# camera_module_dev.net
KiCad netlist of a schematic drawn in EAGLE
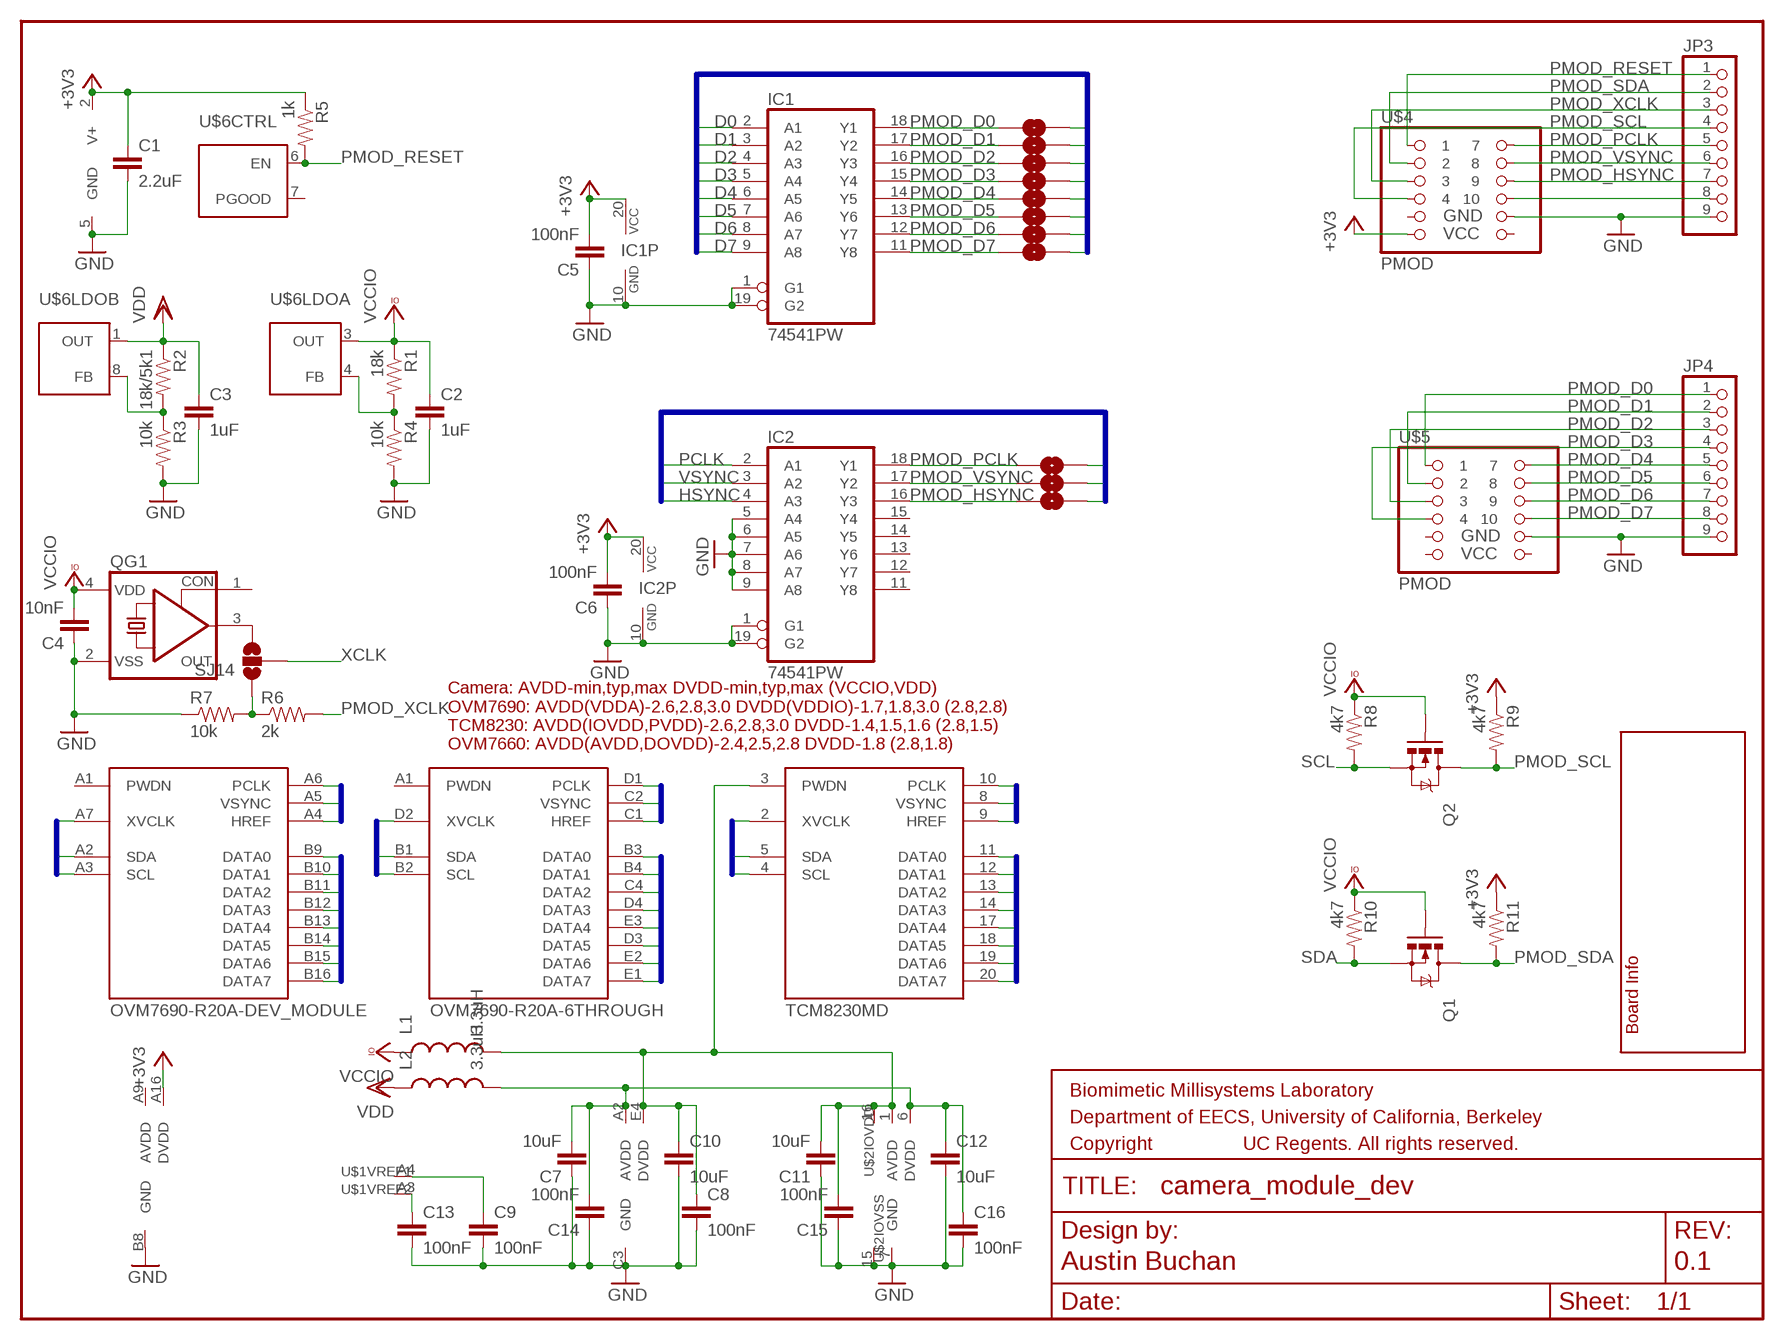
[diagram p0: schematic, sheet 1]

(export (version "E")
  (design (tool "Eeschema 10.0.6"))
  (components
    (comp (ref "C1")
      (value "2.2uF")
      (footprint "eagle-import:0402-CAP")
      (fields (field (name "VOLTAGE") "6.3V"))
      (libsource (lib "eagle-import") (part "CAP0402-CAP"))
    )
    (comp (ref "C2")
      (value "1uF")
      (footprint "eagle-import:0402-CAP")
      (fields (field (name "VOLTAGE") "6.3V"))
      (libsource (lib "eagle-import") (part "CAP0402-CAP"))
    )
    (comp (ref "C3")
      (value "1uF")
      (footprint "eagle-import:0402-CAP")
      (fields (field (name "VOLTAGE") "6.3V"))
      (libsource (lib "eagle-import") (part "CAP0402-CAP"))
    )
    (comp (ref "C4")
      (value "10nF")
      (footprint "eagle-import:0402-CAP")
      (fields (field (name "VOLTAGE") "6.3V"))
      (libsource (lib "eagle-import") (part "CAP0402-CAP"))
    )
    (comp (ref "C5")
      (value "100nF")
      (footprint "eagle-import:0402-CAP")
      (fields (field (name "VOLTAGE") "6.3V"))
      (libsource (lib "eagle-import") (part "CAP0402-CAP"))
    )
    (comp (ref "C6")
      (value "100nF")
      (footprint "eagle-import:0402-CAP")
      (fields (field (name "VOLTAGE") "6.3V"))
      (libsource (lib "eagle-import") (part "CAP0402-CAP"))
    )
    (comp (ref "C7")
      (value "10uF")
      (footprint "eagle-import:0603-CAP")
      (fields (field (name "VOLTAGE") "6.3V"))
      (libsource (lib "eagle-import") (part "CAP0603-CAP"))
    )
    (comp (ref "C8")
      (value "100nF")
      (footprint "eagle-import:0402-CAP")
      (fields (field (name "VOLTAGE") "6.3V"))
      (libsource (lib "eagle-import") (part "CAP0402-CAP"))
    )
    (comp (ref "C9")
      (value "100nF")
      (footprint "eagle-import:0402-CAP")
      (fields (field (name "VOLTAGE") "6.3V"))
      (libsource (lib "eagle-import") (part "CAP0402-CAP"))
    )
    (comp (ref "C10")
      (value "10uF")
      (footprint "eagle-import:0603-CAP")
      (fields (field (name "VOLTAGE") "6.3V"))
      (libsource (lib "eagle-import") (part "CAP0603-CAP"))
    )
    (comp (ref "C11")
      (value "10uF")
      (footprint "eagle-import:0603-CAP")
      (fields (field (name "VOLTAGE") "6.3V"))
      (libsource (lib "eagle-import") (part "CAP0603-CAP"))
    )
    (comp (ref "C12")
      (value "10uF")
      (footprint "eagle-import:0603-CAP")
      (fields (field (name "VOLTAGE") "6.3V"))
      (libsource (lib "eagle-import") (part "CAP0603-CAP"))
    )
    (comp (ref "C13")
      (value "100nF")
      (footprint "eagle-import:0402-CAP")
      (fields (field (name "VOLTAGE") "6.3V"))
      (libsource (lib "eagle-import") (part "CAP0402-CAP"))
    )
    (comp (ref "C14")
      (value "100nF")
      (footprint "eagle-import:0402-CAP")
      (fields (field (name "VOLTAGE") "6.3V"))
      (libsource (lib "eagle-import") (part "CAP0402-CAP"))
    )
    (comp (ref "C15")
      (value "100nF")
      (footprint "eagle-import:0402-CAP")
      (fields (field (name "VOLTAGE") "6.3V"))
      (libsource (lib "eagle-import") (part "CAP0402-CAP"))
    )
    (comp (ref "C16")
      (value "100nF")
      (footprint "eagle-import:0402-CAP")
      (fields (field (name "VOLTAGE") "6.3V"))
      (libsource (lib "eagle-import") (part "CAP0402-CAP"))
    )
    (comp (ref "IC1")
      (value "74541PW")
      (footprint "eagle-import:TSSOP20")
      (libsource (lib "eagle-import") (part "74541PW"))
    )
    (comp (ref "IC2")
      (value "74541PW")
      (footprint "eagle-import:TSSOP20")
      (libsource (lib "eagle-import") (part "74541PW"))
    )
    (comp (ref "JP3")
      (value "PINHD-1X9")
      (footprint "eagle-import:1X09")
      (libsource (lib "eagle-import") (part "PINHD-1X9"))
    )
    (comp (ref "JP4")
      (value "PINHD-1X9")
      (footprint "eagle-import:1X09")
      (libsource (lib "eagle-import") (part "PINHD-1X9"))
    )
    (comp (ref "L1")
      (value "3.3uH")
      (footprint "eagle-import:1007")
      (libsource (lib "eagle-import") (part "INDUCTOR1007"))
    )
    (comp (ref "L2")
      (value "3.3uH")
      (footprint "eagle-import:1007")
      (libsource (lib "eagle-import") (part "INDUCTOR1007"))
    )
    (comp (ref "Q1")
      (value "MOSFET-NCHANNELBSS123LT1G")
      (footprint "eagle-import:SOT23")
      (libsource (lib "eagle-import") (part "MOSFET-NCHANNELBSS123LT1G"))
    )
    (comp (ref "Q2")
      (value "MOSFET-NCHANNELBSS123LT1G")
      (footprint "eagle-import:SOT23")
      (libsource (lib "eagle-import") (part "MOSFET-NCHANNELBSS123LT1G"))
    )
    (comp (ref "QG1")
      (value "CRYSTAL_RES--SMD-4")
      (footprint "eagle-import:SMD-4")
      (libsource (lib "eagle-import") (part "CRYSTAL_RES--SMD-4"))
    )
    (comp (ref "R1")
      (value "18k")
      (footprint "eagle-import:0402-RES")
      (libsource (lib "eagle-import") (part "RESISTOR0402-RES"))
    )
    (comp (ref "R2")
      (value "18k/5k1")
      (footprint "eagle-import:0402-RES")
      (libsource (lib "eagle-import") (part "RESISTOR0402-RES"))
    )
    (comp (ref "R3")
      (value "10k")
      (footprint "eagle-import:0402-RES")
      (libsource (lib "eagle-import") (part "RESISTOR0402-RES"))
    )
    (comp (ref "R4")
      (value "10k")
      (footprint "eagle-import:0402-RES")
      (libsource (lib "eagle-import") (part "RESISTOR0402-RES"))
    )
    (comp (ref "R5")
      (value "1k")
      (footprint "eagle-import:0402-RES")
      (libsource (lib "eagle-import") (part "RESISTOR0402-RES"))
    )
    (comp (ref "R6")
      (value "2k")
      (footprint "eagle-import:0402-RES")
      (libsource (lib "eagle-import") (part "RESISTOR0402-RES"))
    )
    (comp (ref "R7")
      (value "10k")
      (footprint "eagle-import:0402-RES")
      (libsource (lib "eagle-import") (part "RESISTOR0402-RES"))
    )
    (comp (ref "R8")
      (value "4k7")
      (footprint "eagle-import:0402-RES")
      (libsource (lib "eagle-import") (part "RESISTOR0402-RES"))
    )
    (comp (ref "R9")
      (value "4k7")
      (footprint "eagle-import:0402-RES")
      (libsource (lib "eagle-import") (part "RESISTOR0402-RES"))
    )
    (comp (ref "R10")
      (value "4k7")
      (footprint "eagle-import:0402-RES")
      (libsource (lib "eagle-import") (part "RESISTOR0402-RES"))
    )
    (comp (ref "R11")
      (value "4k7")
      (footprint "eagle-import:0402-RES")
      (libsource (lib "eagle-import") (part "RESISTOR0402-RES"))
    )
    (comp (ref "SJ1")
      (value "SOLDERJUMPERNO")
      (footprint "eagle-import:SJ_2S-NO")
      (libsource (lib "eagle-import") (part "SOLDERJUMPERNO"))
    )
    (comp (ref "SJ2")
      (value "SOLDERJUMPERNO")
      (footprint "eagle-import:SJ_2S-NO")
      (libsource (lib "eagle-import") (part "SOLDERJUMPERNO"))
    )
    (comp (ref "SJ3")
      (value "SOLDERJUMPERNO")
      (footprint "eagle-import:SJ_2S-NO")
      (libsource (lib "eagle-import") (part "SOLDERJUMPERNO"))
    )
    (comp (ref "SJ4")
      (value "SOLDERJUMPERNO")
      (footprint "eagle-import:SJ_2S-NO")
      (libsource (lib "eagle-import") (part "SOLDERJUMPERNO"))
    )
    (comp (ref "SJ5")
      (value "SOLDERJUMPERNO")
      (footprint "eagle-import:SJ_2S-NO")
      (libsource (lib "eagle-import") (part "SOLDERJUMPERNO"))
    )
    (comp (ref "SJ6")
      (value "SOLDERJUMPERNO")
      (footprint "eagle-import:SJ_2S-NO")
      (libsource (lib "eagle-import") (part "SOLDERJUMPERNO"))
    )
    (comp (ref "SJ7")
      (value "SOLDERJUMPERNO")
      (footprint "eagle-import:SJ_2S-NO")
      (libsource (lib "eagle-import") (part "SOLDERJUMPERNO"))
    )
    (comp (ref "SJ8")
      (value "SOLDERJUMPERNO")
      (footprint "eagle-import:SJ_2S-NO")
      (libsource (lib "eagle-import") (part "SOLDERJUMPERNO"))
    )
    (comp (ref "SJ9")
      (value "SOLDERJUMPERNO")
      (footprint "eagle-import:SJ_2S-NO")
      (libsource (lib "eagle-import") (part "SOLDERJUMPERNO"))
    )
    (comp (ref "SJ10")
      (value "SOLDERJUMPERNO")
      (footprint "eagle-import:SJ_2S-NO")
      (libsource (lib "eagle-import") (part "SOLDERJUMPERNO"))
    )
    (comp (ref "SJ11")
      (value "SOLDERJUMPERNO")
      (footprint "eagle-import:SJ_2S-NO")
      (libsource (lib "eagle-import") (part "SOLDERJUMPERNO"))
    )
    (comp (ref "SJ14")
      (value "SOLDERJUMPER_2WAYS")
      (footprint "eagle-import:SJ_3")
      (libsource (lib "eagle-import") (part "SOLDERJUMPER_2WAYS"))
    )
    (comp (ref "U$1")
      (value "OVM7690-R20A-6THROUGH")
      (footprint "eagle-import:CSP3-20-6THROUGH")
      (libsource (lib "eagle-import") (part "OVM7690-R20A-6THROUGH"))
    )
    (comp (ref "U$2")
      (value "TCM8230MD")
      (footprint "eagle-import:TCM-20")
      (libsource (lib "eagle-import") (part "TCM8230MD"))
    )
    (comp (ref "U$3")
      (value "OVM7690-R20A-DEV_MODULE")
      (footprint "eagle-import:OVM_DEV_MODULE")
      (libsource (lib "eagle-import") (part "OVM7690-R20A-DEV_MODULE"))
    )
    (comp (ref "U$4")
      (value "PMOD")
      (footprint "eagle-import:2X06")
      (libsource (lib "eagle-import") (part "PMOD"))
    )
    (comp (ref "U$5")
      (value "PMOD")
      (footprint "eagle-import:2X06")
      (libsource (lib "eagle-import") (part "PMOD"))
    )
    (comp (ref "U$6")
      (value "SC560C")
      (footprint "eagle-import:MLPQ-UT8")
      (libsource (lib "eagle-import") (part "SC560C"))
    )
    (comp (ref "U$7")
      (value "INFO")
      (footprint "eagle-import:INFO")
      (fields
        (field (name "AUTHOR") "Austin Buchan")
        (field (name "DATE") "Feb. 2014")
        (field (name "DESIGN") "Dev Camera Module")
        (field (name "ORGANIZATION") "UC Berkeley Biomimetic Millisystems Lab")
        (field (name "REVISION") "r0.1")
      )
      (libsource (lib "eagle-import") (part "INFO"))
    )
  )
  (nets
    (net (code "1") (name "+3V3") (class "Default")
      (node (ref "C1") (pin "1") (pinfunction "1_1") (pintype "passive"))
      (node (ref "C5") (pin "2") (pinfunction "2_2") (pintype "passive"))
      (node (ref "C6") (pin "2") (pinfunction "2_2") (pintype "passive"))
      (node (ref "IC1") (pin "20") (pinfunction "VCC_20") (pintype "power_in"))
      (node (ref "IC2") (pin "20") (pinfunction "VCC_20") (pintype "power_in"))
      (node (ref "R11") (pin "1") (pinfunction "1_1") (pintype "passive"))
      (node (ref "R5") (pin "1") (pinfunction "1_1") (pintype "passive"))
      (node (ref "R9") (pin "1") (pinfunction "1_1") (pintype "passive"))
      (node (ref "U$3") (pin "A16") (pinfunction "DVDD_A16") (pintype "power_in"))
      (node (ref "U$4") (pin "11") (pinfunction "6_11") (pintype "passive"))
      (node (ref "U$6") (pin "2") (pinfunction "V+_2") (pintype "power_in"))
    )
    (net (code "2") (name "/AVDD") (class "Default")
      (node (ref "U$3") (pin "A9") (pinfunction "AVDD_A9") (pintype "power_in"))
    )
    (net (code "3") (name "/D0") (class "Default")
      (node (ref "IC1") (pin "2") (pinfunction "A1_2") (pintype "input"))
      (node (ref "SJ1") (pin "2") (pinfunction "2_2") (pintype "passive"))
      (node (ref "U$1") (pin "B3") (pinfunction "DATA0_B3") (pintype "bidirectional"))
      (node (ref "U$2") (pin "11") (pinfunction "DATA0_11") (pintype "bidirectional"))
      (node (ref "U$3") (pin "B9") (pinfunction "DATA0_B9") (pintype "bidirectional"))
    )
    (net (code "4") (name "/D1") (class "Default")
      (node (ref "IC1") (pin "3") (pinfunction "A2_3") (pintype "input"))
      (node (ref "SJ2") (pin "2") (pinfunction "2_2") (pintype "passive"))
      (node (ref "U$1") (pin "B4") (pinfunction "DATA1_B4") (pintype "bidirectional"))
      (node (ref "U$2") (pin "12") (pinfunction "DATA1_12") (pintype "bidirectional"))
      (node (ref "U$3") (pin "B10") (pinfunction "DATA1_B10") (pintype "bidirectional"))
    )
    (net (code "5") (name "/D2") (class "Default")
      (node (ref "IC1") (pin "4") (pinfunction "A3_4") (pintype "input"))
      (node (ref "SJ3") (pin "2") (pinfunction "2_2") (pintype "passive"))
      (node (ref "U$1") (pin "C4") (pinfunction "DATA2_C4") (pintype "bidirectional"))
      (node (ref "U$2") (pin "13") (pinfunction "DATA2_13") (pintype "bidirectional"))
      (node (ref "U$3") (pin "B11") (pinfunction "DATA2_B11") (pintype "bidirectional"))
    )
    (net (code "6") (name "/D3") (class "Default")
      (node (ref "IC1") (pin "5") (pinfunction "A4_5") (pintype "input"))
      (node (ref "SJ4") (pin "2") (pinfunction "2_2") (pintype "passive"))
      (node (ref "U$1") (pin "D4") (pinfunction "DATA3_D4") (pintype "bidirectional"))
      (node (ref "U$2") (pin "14") (pinfunction "DATA3_14") (pintype "bidirectional"))
      (node (ref "U$3") (pin "B12") (pinfunction "DATA3_B12") (pintype "bidirectional"))
    )
    (net (code "7") (name "/D4") (class "Default")
      (node (ref "IC1") (pin "6") (pinfunction "A5_6") (pintype "input"))
      (node (ref "SJ5") (pin "2") (pinfunction "2_2") (pintype "passive"))
      (node (ref "U$1") (pin "E3") (pinfunction "DATA4_E3") (pintype "bidirectional"))
      (node (ref "U$2") (pin "17") (pinfunction "DATA4_17") (pintype "bidirectional"))
      (node (ref "U$3") (pin "B13") (pinfunction "DATA4_B13") (pintype "bidirectional"))
    )
    (net (code "8") (name "/D5") (class "Default")
      (node (ref "IC1") (pin "7") (pinfunction "A6_7") (pintype "input"))
      (node (ref "SJ6") (pin "2") (pinfunction "2_2") (pintype "passive"))
      (node (ref "U$1") (pin "D3") (pinfunction "DATA5_D3") (pintype "bidirectional"))
      (node (ref "U$2") (pin "18") (pinfunction "DATA5_18") (pintype "bidirectional"))
      (node (ref "U$3") (pin "B14") (pinfunction "DATA5_B14") (pintype "bidirectional"))
    )
    (net (code "9") (name "/D6") (class "Default")
      (node (ref "IC1") (pin "8") (pinfunction "A7_8") (pintype "input"))
      (node (ref "SJ7") (pin "2") (pinfunction "2_2") (pintype "passive"))
      (node (ref "U$1") (pin "E2") (pinfunction "DATA6_E2") (pintype "bidirectional"))
      (node (ref "U$2") (pin "19") (pinfunction "DATA6_19") (pintype "bidirectional"))
      (node (ref "U$3") (pin "B15") (pinfunction "DATA6_B15") (pintype "bidirectional"))
    )
    (net (code "10") (name "/D7") (class "Default")
      (node (ref "IC1") (pin "9") (pinfunction "A8_9") (pintype "input"))
      (node (ref "SJ8") (pin "2") (pinfunction "2_2") (pintype "passive"))
      (node (ref "U$1") (pin "E1") (pinfunction "DATA7_E1") (pintype "bidirectional"))
      (node (ref "U$2") (pin "20") (pinfunction "DATA7_20") (pintype "bidirectional"))
      (node (ref "U$3") (pin "B16") (pinfunction "DATA7_B16") (pintype "bidirectional"))
    )
    (net (code "11") (name "/HSYNC") (class "Default")
      (node (ref "IC2") (pin "4") (pinfunction "A3_4") (pintype "input"))
      (node (ref "SJ11") (pin "2") (pinfunction "2_2") (pintype "passive"))
      (node (ref "U$1") (pin "C1") (pinfunction "HREF_C1") (pintype "bidirectional"))
      (node (ref "U$2") (pin "9") (pinfunction "HREF_9") (pintype "bidirectional"))
      (node (ref "U$3") (pin "A4") (pinfunction "HREF_A4") (pintype "bidirectional"))
    )
    (net (code "12") (name "/PCLK") (class "Default")
      (node (ref "IC2") (pin "2") (pinfunction "A1_2") (pintype "input"))
      (node (ref "SJ9") (pin "2") (pinfunction "2_2") (pintype "passive"))
      (node (ref "U$1") (pin "D1") (pinfunction "PCLK_D1") (pintype "bidirectional"))
      (node (ref "U$2") (pin "10") (pinfunction "PCLK_10") (pintype "bidirectional"))
      (node (ref "U$3") (pin "A6") (pinfunction "PCLK_A6") (pintype "bidirectional"))
    )
    (net (code "13") (name "/PMOD_D0") (class "Default")
      (node (ref "IC1") (pin "18") (pinfunction "Y1_18") (pintype "tri_state"))
      (node (ref "JP4") (pin "1") (pinfunction "1_1") (pintype "passive"))
      (node (ref "SJ1") (pin "1") (pinfunction "1_1") (pintype "passive"))
      (node (ref "U$5") (pin "1") (pinfunction "1_1") (pintype "passive"))
    )
    (net (code "14") (name "/PMOD_D1") (class "Default")
      (node (ref "IC1") (pin "17") (pinfunction "Y2_17") (pintype "tri_state"))
      (node (ref "JP4") (pin "2") (pinfunction "2_2") (pintype "passive"))
      (node (ref "SJ2") (pin "1") (pinfunction "1_1") (pintype "passive"))
      (node (ref "U$5") (pin "3") (pinfunction "2_3") (pintype "passive"))
    )
    (net (code "15") (name "/PMOD_D2") (class "Default")
      (node (ref "IC1") (pin "16") (pinfunction "Y3_16") (pintype "tri_state"))
      (node (ref "JP4") (pin "3") (pinfunction "3_3") (pintype "passive"))
      (node (ref "SJ3") (pin "1") (pinfunction "1_1") (pintype "passive"))
      (node (ref "U$5") (pin "5") (pinfunction "3_5") (pintype "passive"))
    )
    (net (code "16") (name "/PMOD_D3") (class "Default")
      (node (ref "IC1") (pin "15") (pinfunction "Y4_15") (pintype "tri_state"))
      (node (ref "JP4") (pin "4") (pinfunction "4_4") (pintype "passive"))
      (node (ref "SJ4") (pin "1") (pinfunction "1_1") (pintype "passive"))
      (node (ref "U$5") (pin "7") (pinfunction "4_7") (pintype "passive"))
    )
    (net (code "17") (name "/PMOD_D4") (class "Default")
      (node (ref "IC1") (pin "14") (pinfunction "Y5_14") (pintype "tri_state"))
      (node (ref "JP4") (pin "5") (pinfunction "5_5") (pintype "passive"))
      (node (ref "SJ5") (pin "1") (pinfunction "1_1") (pintype "passive"))
      (node (ref "U$5") (pin "2") (pinfunction "7_2") (pintype "passive"))
    )
    (net (code "18") (name "/PMOD_D5") (class "Default")
      (node (ref "IC1") (pin "13") (pinfunction "Y6_13") (pintype "tri_state"))
      (node (ref "JP4") (pin "6") (pinfunction "6_6") (pintype "passive"))
      (node (ref "SJ6") (pin "1") (pinfunction "1_1") (pintype "passive"))
      (node (ref "U$5") (pin "4") (pinfunction "8_4") (pintype "passive"))
    )
    (net (code "19") (name "/PMOD_D6") (class "Default")
      (node (ref "IC1") (pin "12") (pinfunction "Y7_12") (pintype "tri_state"))
      (node (ref "JP4") (pin "7") (pinfunction "7_7") (pintype "passive"))
      (node (ref "SJ7") (pin "1") (pinfunction "1_1") (pintype "passive"))
      (node (ref "U$5") (pin "6") (pinfunction "9_6") (pintype "passive"))
    )
    (net (code "20") (name "/PMOD_D7") (class "Default")
      (node (ref "IC1") (pin "11") (pinfunction "Y8_11") (pintype "tri_state"))
      (node (ref "JP4") (pin "8") (pinfunction "8_8") (pintype "passive"))
      (node (ref "SJ8") (pin "1") (pinfunction "1_1") (pintype "passive"))
      (node (ref "U$5") (pin "8") (pinfunction "10_8") (pintype "passive"))
    )
    (net (code "21") (name "/PMOD_HSYNC") (class "Default")
      (node (ref "IC2") (pin "16") (pinfunction "Y3_16") (pintype "tri_state"))
      (node (ref "JP3") (pin "7") (pinfunction "7_7") (pintype "passive"))
      (node (ref "SJ11") (pin "1") (pinfunction "1_1") (pintype "passive"))
      (node (ref "U$4") (pin "6") (pinfunction "9_6") (pintype "passive"))
    )
    (net (code "22") (name "/PMOD_PCLK") (class "Default")
      (node (ref "IC2") (pin "18") (pinfunction "Y1_18") (pintype "tri_state"))
      (node (ref "JP3") (pin "5") (pinfunction "5_5") (pintype "passive"))
      (node (ref "SJ9") (pin "1") (pinfunction "1_1") (pintype "passive"))
      (node (ref "U$4") (pin "2") (pinfunction "7_2") (pintype "passive"))
    )
    (net (code "23") (name "/PMOD_RESET") (class "Default")
      (node (ref "JP3") (pin "1") (pinfunction "1_1") (pintype "passive"))
      (node (ref "R5") (pin "2") (pinfunction "2_2") (pintype "passive"))
      (node (ref "U$4") (pin "1") (pinfunction "1_1") (pintype "passive"))
      (node (ref "U$6") (pin "6") (pinfunction "EN_6") (pintype "bidirectional"))
    )
    (net (code "24") (name "/PMOD_SCL") (class "Default")
      (node (ref "JP3") (pin "4") (pinfunction "4_4") (pintype "passive"))
      (node (ref "Q2") (pin "3") (pinfunction "D_3") (pintype "passive"))
      (node (ref "R9") (pin "2") (pinfunction "2_2") (pintype "passive"))
      (node (ref "U$4") (pin "7") (pinfunction "4_7") (pintype "passive"))
    )
    (net (code "25") (name "/PMOD_SDA") (class "Default")
      (node (ref "JP3") (pin "2") (pinfunction "2_2") (pintype "passive"))
      (node (ref "Q1") (pin "3") (pinfunction "D_3") (pintype "passive"))
      (node (ref "R11") (pin "2") (pinfunction "2_2") (pintype "passive"))
      (node (ref "U$4") (pin "3") (pinfunction "2_3") (pintype "passive"))
    )
    (net (code "26") (name "/PMOD_VSYNC") (class "Default")
      (node (ref "IC2") (pin "17") (pinfunction "Y2_17") (pintype "tri_state"))
      (node (ref "JP3") (pin "6") (pinfunction "6_6") (pintype "passive"))
      (node (ref "SJ10") (pin "1") (pinfunction "1_1") (pintype "passive"))
      (node (ref "U$4") (pin "4") (pinfunction "8_4") (pintype "passive"))
    )
    (net (code "27") (name "/PMOD_XCLK") (class "Default")
      (node (ref "JP3") (pin "3") (pinfunction "3_3") (pintype "passive"))
      (node (ref "R6") (pin "2") (pinfunction "2_2") (pintype "passive"))
      (node (ref "U$4") (pin "5") (pinfunction "3_5") (pintype "passive"))
    )
    (net (code "28") (name "/SCL") (class "Default")
      (node (ref "Q2") (pin "2") (pinfunction "S_2") (pintype "passive"))
      (node (ref "R8") (pin "2") (pinfunction "2_2") (pintype "passive"))
      (node (ref "U$1") (pin "B2") (pinfunction "SCL_B2") (pintype "bidirectional"))
      (node (ref "U$2") (pin "4") (pinfunction "SCL_4") (pintype "bidirectional"))
      (node (ref "U$3") (pin "A3") (pinfunction "SCL_A3") (pintype "bidirectional"))
    )
    (net (code "29") (name "/SDA") (class "Default")
      (node (ref "Q1") (pin "2") (pinfunction "S_2") (pintype "passive"))
      (node (ref "R10") (pin "2") (pinfunction "2_2") (pintype "passive"))
      (node (ref "U$1") (pin "B1") (pinfunction "SDA_B1") (pintype "bidirectional"))
      (node (ref "U$2") (pin "5") (pinfunction "SDA_5") (pintype "bidirectional"))
      (node (ref "U$3") (pin "A2") (pinfunction "SDA_A2") (pintype "bidirectional"))
    )
    (net (code "30") (name "/VSYNC") (class "Default")
      (node (ref "IC2") (pin "3") (pinfunction "A2_3") (pintype "input"))
      (node (ref "SJ10") (pin "2") (pinfunction "2_2") (pintype "passive"))
      (node (ref "U$1") (pin "C2") (pinfunction "VSYNC_C2") (pintype "bidirectional"))
      (node (ref "U$2") (pin "8") (pinfunction "VSYNC_8") (pintype "bidirectional"))
      (node (ref "U$3") (pin "A5") (pinfunction "VSYNC_A5") (pintype "bidirectional"))
    )
    (net (code "31") (name "/XCLK") (class "Default")
      (node (ref "SJ14") (pin "2") (pinfunction "2_2") (pintype "passive"))
      (node (ref "U$1") (pin "D2") (pinfunction "XVCLK_D2") (pintype "bidirectional"))
      (node (ref "U$2") (pin "2") (pinfunction "XVCLK_2") (pintype "bidirectional"))
      (node (ref "U$3") (pin "A7") (pinfunction "XVCLK_A7") (pintype "bidirectional"))
    )
    (net (code "32") (name "GND") (class "Default")
      (node (ref "C1") (pin "2") (pinfunction "2_2") (pintype "passive"))
      (node (ref "C10") (pin "2") (pinfunction "2_2") (pintype "passive"))
      (node (ref "C11") (pin "1") (pinfunction "1_1") (pintype "passive"))
      (node (ref "C12") (pin "2") (pinfunction "2_2") (pintype "passive"))
      (node (ref "C13") (pin "2") (pinfunction "2_2") (pintype "passive"))
      (node (ref "C14") (pin "1") (pinfunction "1_1") (pintype "passive"))
      (node (ref "C15") (pin "1") (pinfunction "1_1") (pintype "passive"))
      (node (ref "C16") (pin "2") (pinfunction "2_2") (pintype "passive"))
      (node (ref "C2") (pin "2") (pinfunction "2_2") (pintype "passive"))
      (node (ref "C3") (pin "2") (pinfunction "2_2") (pintype "passive"))
      (node (ref "C4") (pin "1") (pinfunction "1_1") (pintype "passive"))
      (node (ref "C5") (pin "1") (pinfunction "1_1") (pintype "passive"))
      (node (ref "C6") (pin "1") (pinfunction "1_1") (pintype "passive"))
      (node (ref "C7") (pin "1") (pinfunction "1_1") (pintype "passive"))
      (node (ref "C8") (pin "2") (pinfunction "2_2") (pintype "passive"))
      (node (ref "C9") (pin "2") (pinfunction "2_2") (pintype "passive"))
      (node (ref "IC1") (pin "1") (pinfunction "G1_1") (pintype "input"))
      (node (ref "IC1") (pin "10") (pinfunction "GND_10") (pintype "power_in"))
      (node (ref "IC1") (pin "19") (pinfunction "G2_19") (pintype "input"))
      (node (ref "IC2") (pin "1") (pinfunction "G1_1") (pintype "input"))
      (node (ref "IC2") (pin "10") (pinfunction "GND_10") (pintype "power_in"))
      (node (ref "IC2") (pin "19") (pinfunction "G2_19") (pintype "input"))
      (node (ref "IC2") (pin "5") (pinfunction "A4_5") (pintype "input"))
      (node (ref "IC2") (pin "6") (pinfunction "A5_6") (pintype "input"))
      (node (ref "IC2") (pin "7") (pinfunction "A6_7") (pintype "input"))
      (node (ref "IC2") (pin "8") (pinfunction "A7_8") (pintype "input"))
      (node (ref "IC2") (pin "9") (pinfunction "A8_9") (pintype "input"))
      (node (ref "JP3") (pin "9") (pinfunction "9_9") (pintype "passive"))
      (node (ref "JP4") (pin "9") (pinfunction "9_9") (pintype "passive"))
      (node (ref "QG1") (pin "2") (pinfunction "VSS_2") (pintype "power_in"))
      (node (ref "R3") (pin "2") (pinfunction "2_2") (pintype "passive"))
      (node (ref "R4") (pin "2") (pinfunction "2_2") (pintype "passive"))
      (node (ref "R7") (pin "1") (pinfunction "1_1") (pintype "passive"))
      (node (ref "U$1") (pin "C3") (pinfunction "GND_C3") (pintype "power_in"))
      (node (ref "U$2") (pin "15") (pinfunction "V_15") (pintype "power_in"))
      (node (ref "U$2") (pin "7") (pinfunction "GND_7") (pintype "power_in"))
      (node (ref "U$3") (pin "B8") (pinfunction "GND_B8") (pintype "power_in"))
      (node (ref "U$4") (pin "10") (pinfunction "11_10") (pintype "passive"))
      (node (ref "U$5") (pin "10") (pinfunction "11_10") (pintype "passive"))
      (node (ref "U$6") (pin "5") (pinfunction "GND_5") (pintype "power_in"))
    )
    (net (code "33") (name "Net-(QG1-OUT)") (class "Default")
      (node (ref "QG1") (pin "3") (pinfunction "OUT_3") (pintype "output"))
      (node (ref "SJ14") (pin "3") (pinfunction "3_3") (pintype "passive"))
    )
    (net (code "34") (name "Net-(R6-Pad1)") (class "Default")
      (node (ref "R6") (pin "1") (pinfunction "1_1") (pintype "passive"))
      (node (ref "R7") (pin "2") (pinfunction "2_2") (pintype "passive"))
      (node (ref "SJ14") (pin "1") (pinfunction "1_1") (pintype "passive"))
    )
    (net (code "35") (name "Net-(U$1B-AVDD)") (class "Default")
      (node (ref "C12") (pin "1") (pinfunction "1_1") (pintype "passive"))
      (node (ref "C14") (pin "2") (pinfunction "2_2") (pintype "passive"))
      (node (ref "C16") (pin "1") (pinfunction "1_1") (pintype "passive"))
      (node (ref "C7") (pin "2") (pinfunction "2_2") (pintype "passive"))
      (node (ref "L2") (pin "2") (pinfunction "2_2") (pintype "passive"))
      (node (ref "U$1") (pin "A2") (pinfunction "AVDD_A2") (pintype "power_in"))
      (node (ref "U$2") (pin "6") (pinfunction "DVDD_6") (pintype "power_in"))
    )
    (net (code "36") (name "Net-(U$1B-DVDD)") (class "Default")
      (node (ref "C10") (pin "1") (pinfunction "1_1") (pintype "passive"))
      (node (ref "C11") (pin "2") (pinfunction "2_2") (pintype "passive"))
      (node (ref "C15") (pin "2") (pinfunction "2_2") (pintype "passive"))
      (node (ref "C8") (pin "1") (pinfunction "1_1") (pintype "passive"))
      (node (ref "L1") (pin "2") (pinfunction "2_2") (pintype "passive"))
      (node (ref "U$1") (pin "E4") (pinfunction "DVDD_E4") (pintype "power_in"))
      (node (ref "U$2") (pin "1") (pinfunction "AVDD_1") (pintype "power_in"))
      (node (ref "U$2") (pin "16") (pinfunction "V_16") (pintype "power_in"))
      (node (ref "U$2") (pin "3") (pinfunction "PWDN_3") (pintype "bidirectional"))
    )
    (net (code "37") (name "Net-(U$1C-V)") (class "Default")
      (node (ref "C9") (pin "1") (pinfunction "1_1") (pintype "passive"))
      (node (ref "U$1") (pin "A4") (pinfunction "V_A4") (pintype "power_in"))
    )
    (net (code "38") (name "Net-(U$1D-V)") (class "Default")
      (node (ref "C13") (pin "1") (pinfunction "1_1") (pintype "passive"))
      (node (ref "U$1") (pin "A3") (pinfunction "V_A3") (pintype "power_in"))
    )
    (net (code "39") (name "Net-(U$4-10)") (class "Default")
      (node (ref "JP3") (pin "8") (pinfunction "8_8") (pintype "passive"))
      (node (ref "U$4") (pin "8") (pinfunction "10_8") (pintype "passive"))
    )
    (net (code "40") (name "Net-(U$6C-FB)") (class "Default")
      (node (ref "R1") (pin "2") (pinfunction "2_2") (pintype "passive"))
      (node (ref "R4") (pin "1") (pinfunction "1_1") (pintype "passive"))
      (node (ref "U$6") (pin "4") (pinfunction "FB_4") (pintype "bidirectional"))
    )
    (net (code "41") (name "Net-(U$6D-FB)") (class "Default")
      (node (ref "R2") (pin "2") (pinfunction "2_2") (pintype "passive"))
      (node (ref "R3") (pin "1") (pinfunction "1_1") (pintype "passive"))
      (node (ref "U$6") (pin "8") (pinfunction "FB_8") (pintype "bidirectional"))
    )
    (net (code "42") (name "VCCIO") (class "Default")
      (node (ref "C2") (pin "1") (pinfunction "1_1") (pintype "passive"))
      (node (ref "C4") (pin "2") (pinfunction "2_2") (pintype "passive"))
      (node (ref "L1") (pin "1") (pinfunction "1_1") (pintype "passive"))
      (node (ref "Q1") (pin "1") (pinfunction "G_1") (pintype "passive"))
      (node (ref "Q2") (pin "1") (pinfunction "G_1") (pintype "passive"))
      (node (ref "QG1") (pin "4") (pinfunction "VDD_4") (pintype "power_in"))
      (node (ref "R1") (pin "1") (pinfunction "1_1") (pintype "passive"))
      (node (ref "R10") (pin "1") (pinfunction "1_1") (pintype "passive"))
      (node (ref "R8") (pin "1") (pinfunction "1_1") (pintype "passive"))
      (node (ref "U$6") (pin "3") (pinfunction "OUT_3") (pintype "bidirectional"))
    )
    (net (code "43") (name "VDD") (class "Default")
      (node (ref "C3") (pin "1") (pinfunction "1_1") (pintype "passive"))
      (node (ref "L2") (pin "1") (pinfunction "1_1") (pintype "passive"))
      (node (ref "R2") (pin "1") (pinfunction "1_1") (pintype "passive"))
      (node (ref "U$6") (pin "1") (pinfunction "OUT_1") (pintype "bidirectional"))
    )
    (net (code "44") (name "unconnected-(IC2A-Y4-Pad15)") (class "Default")
      (node (ref "IC2") (pin "15") (pinfunction "Y4_15") (pintype "tri_state"))
    )
    (net (code "45") (name "unconnected-(IC2A-Y5-Pad14)") (class "Default")
      (node (ref "IC2") (pin "14") (pinfunction "Y5_14") (pintype "tri_state"))
    )
    (net (code "46") (name "unconnected-(IC2A-Y6-Pad13)") (class "Default")
      (node (ref "IC2") (pin "13") (pinfunction "Y6_13") (pintype "tri_state"))
    )
    (net (code "47") (name "unconnected-(IC2A-Y7-Pad12)") (class "Default")
      (node (ref "IC2") (pin "12") (pinfunction "Y7_12") (pintype "tri_state"))
    )
    (net (code "48") (name "unconnected-(IC2A-Y8-Pad11)") (class "Default")
      (node (ref "IC2") (pin "11") (pinfunction "Y8_11") (pintype "tri_state"))
    )
    (net (code "49") (name "unconnected-(QG1-CON-Pad1)") (class "Default")
      (node (ref "QG1") (pin "1") (pinfunction "CON_1") (pintype "input"))
    )
    (net (code "50") (name "unconnected-(U$1A-PWDN-PadA1)") (class "Default")
      (node (ref "U$1") (pin "A1") (pinfunction "PWDN_A1") (pintype "bidirectional"))
    )
    (net (code "51") (name "unconnected-(U$3A-PWDN-PadA1)") (class "Default")
      (node (ref "U$3") (pin "A1") (pinfunction "PWDN_A1") (pintype "bidirectional"))
    )
    (net (code "52") (name "unconnected-(U$4-5-Pad9)") (class "Default")
      (node (ref "U$4") (pin "9") (pinfunction "5_9") (pintype "passive"))
    )
    (net (code "53") (name "unconnected-(U$4-Pad12)") (class "Default")
      (node (ref "U$4") (pin "12") (pinfunction "12_12") (pintype "passive"))
    )
    (net (code "54") (name "unconnected-(U$5-5-Pad9)") (class "Default")
      (node (ref "U$5") (pin "9") (pinfunction "5_9") (pintype "passive"))
    )
    (net (code "55") (name "unconnected-(U$5-6-Pad11)") (class "Default")
      (node (ref "U$5") (pin "11") (pinfunction "6_11") (pintype "passive"))
    )
    (net (code "56") (name "unconnected-(U$5-Pad12)") (class "Default")
      (node (ref "U$5") (pin "12") (pinfunction "12_12") (pintype "passive"))
    )
    (net (code "57") (name "unconnected-(U$6A-PGOOD-Pad7)") (class "Default")
      (node (ref "U$6") (pin "7") (pinfunction "PGOOD_7") (pintype "bidirectional"))
    )
  )
)
